# 2_channel_DIP.net
KiCad netlist of a schematic drawn in EAGLE
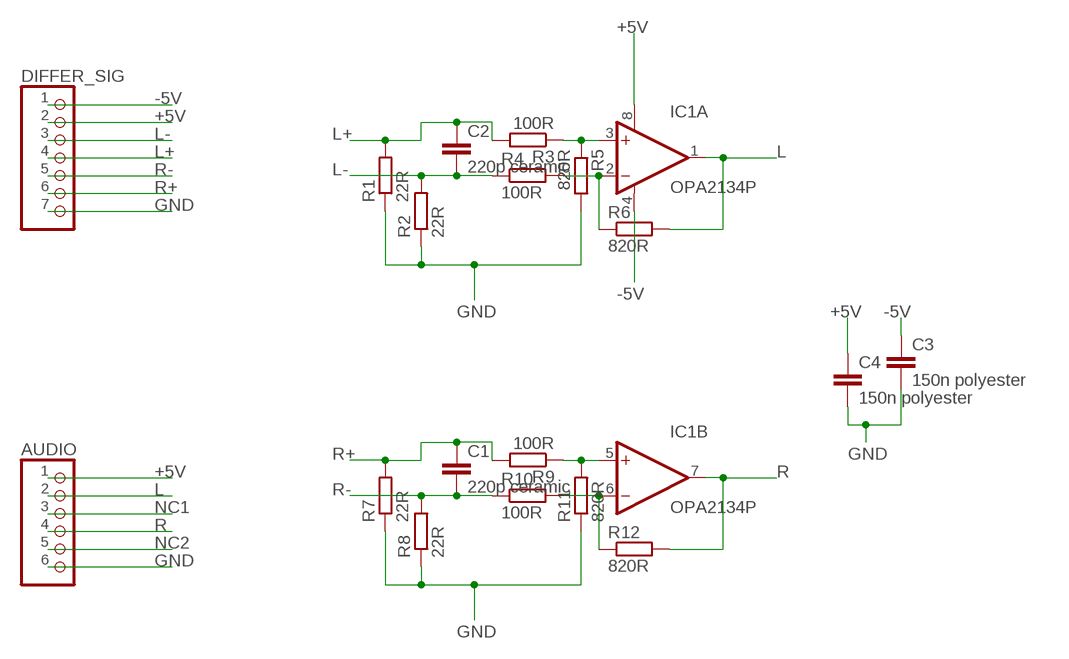
[diagram p0: schematic, sheet 1]

(export (version "E")
  (design (tool "Eeschema 10.0.6"))
  (components
    (comp (ref "AUDIO")
      (value "PINHD-1X6")
      (footprint "eagle-import:1X06")
      (libsource (lib "eagle-import") (part "PINHD-1X6"))
    )
    (comp (ref "C1")
      (value "220p ceramic")
      (footprint "eagle-import:C050-030X075")
      (libsource (lib "eagle-import") (part "C-EU050-030X075"))
    )
    (comp (ref "C2")
      (value "220p ceramic")
      (footprint "eagle-import:C050-030X075")
      (libsource (lib "eagle-import") (part "C-EU050-030X075"))
    )
    (comp (ref "C3")
      (value "150n polyester")
      (footprint "eagle-import:C050-030X075")
      (libsource (lib "eagle-import") (part "C-EU050-030X075"))
    )
    (comp (ref "C4")
      (value "150n polyester")
      (footprint "eagle-import:C050-030X075")
      (libsource (lib "eagle-import") (part "C-EU050-030X075"))
    )
    (comp (ref "DIFFER_SIG")
      (value "PINHD-1X7")
      (footprint "eagle-import:1X07")
      (libsource (lib "eagle-import") (part "PINHD-1X7"))
    )
    (comp (ref "IC1")
      (value "OPA2134P")
      (footprint "eagle-import:DIL08")
      (fields (field (name "MF") "TEXAS INSTRUMENTS") (field (name "MPN") "OPA2134PA"))
      (libsource (lib "eagle-import") (part "OPA2134P"))
    )
    (comp (ref "R1")
      (value "22R")
      (footprint "eagle-import:0207_7")
      (libsource (lib "eagle-import") (part "R-EU_0207/7"))
    )
    (comp (ref "R2")
      (value "22R")
      (footprint "eagle-import:0207_7")
      (libsource (lib "eagle-import") (part "R-EU_0207/7"))
    )
    (comp (ref "R3")
      (value "100R")
      (footprint "eagle-import:0207_7")
      (libsource (lib "eagle-import") (part "R-EU_0207/7"))
    )
    (comp (ref "R4")
      (value "100R")
      (footprint "eagle-import:0207_7")
      (libsource (lib "eagle-import") (part "R-EU_0207/7"))
    )
    (comp (ref "R5")
      (value "820R")
      (footprint "eagle-import:0207_7")
      (libsource (lib "eagle-import") (part "R-EU_0207/7"))
    )
    (comp (ref "R6")
      (value "820R")
      (footprint "eagle-import:0207_7")
      (libsource (lib "eagle-import") (part "R-EU_0207/7"))
    )
    (comp (ref "R7")
      (value "22R")
      (footprint "eagle-import:0207_7")
      (libsource (lib "eagle-import") (part "R-EU_0207/7"))
    )
    (comp (ref "R8")
      (value "22R")
      (footprint "eagle-import:0207_7")
      (libsource (lib "eagle-import") (part "R-EU_0207/7"))
    )
    (comp (ref "R9")
      (value "100R")
      (footprint "eagle-import:0207_7")
      (libsource (lib "eagle-import") (part "R-EU_0207/7"))
    )
    (comp (ref "R10")
      (value "100R")
      (footprint "eagle-import:0207_7")
      (libsource (lib "eagle-import") (part "R-EU_0207/7"))
    )
    (comp (ref "R11")
      (value "820R")
      (footprint "eagle-import:0207_7")
      (libsource (lib "eagle-import") (part "R-EU_0207/7"))
    )
    (comp (ref "R12")
      (value "820R")
      (footprint "eagle-import:0207_7")
      (libsource (lib "eagle-import") (part "R-EU_0207/7"))
    )
  )
  (nets
    (net (code "1") (name "/+5V") (class "Default")
      (node (ref "AUDIO") (pin "1") (pinfunction "1_1") (pintype "passive"))
      (node (ref "C4") (pin "1") (pinfunction "1_1") (pintype "passive"))
      (node (ref "DIFFER_SIG") (pin "2") (pinfunction "2_2") (pintype "passive"))
      (node (ref "IC1") (pin "8") (pinfunction "V+_8") (pintype "power_in"))
    )
    (net (code "2") (name "/-5V") (class "Default")
      (node (ref "C3") (pin "1") (pinfunction "1_1") (pintype "passive"))
      (node (ref "DIFFER_SIG") (pin "1") (pinfunction "1_1") (pintype "passive"))
      (node (ref "IC1") (pin "4") (pinfunction "V-_4") (pintype "power_in"))
    )
    (net (code "3") (name "/GND") (class "Default")
      (node (ref "AUDIO") (pin "6") (pinfunction "6_6") (pintype "passive"))
      (node (ref "C3") (pin "2") (pinfunction "2_2") (pintype "passive"))
      (node (ref "C4") (pin "2") (pinfunction "2_2") (pintype "passive"))
      (node (ref "DIFFER_SIG") (pin "7") (pinfunction "7_7") (pintype "passive"))
      (node (ref "R1") (pin "1") (pinfunction "1_1") (pintype "passive"))
      (node (ref "R11") (pin "1") (pinfunction "1_1") (pintype "passive"))
      (node (ref "R2") (pin "1") (pinfunction "1_1") (pintype "passive"))
      (node (ref "R5") (pin "2") (pinfunction "2_2") (pintype "passive"))
      (node (ref "R7") (pin "1") (pinfunction "1_1") (pintype "passive"))
      (node (ref "R8") (pin "1") (pinfunction "1_1") (pintype "passive"))
    )
    (net (code "4") (name "/L") (class "Default")
      (node (ref "AUDIO") (pin "2") (pinfunction "2_2") (pintype "passive"))
      (node (ref "IC1") (pin "1") (pinfunction "OUT_1") (pintype "output"))
      (node (ref "R6") (pin "2") (pinfunction "2_2") (pintype "passive"))
    )
    (net (code "5") (name "/L+") (class "Default")
      (node (ref "C2") (pin "1") (pinfunction "1_1") (pintype "passive"))
      (node (ref "DIFFER_SIG") (pin "4") (pinfunction "4_4") (pintype "passive"))
      (node (ref "R1") (pin "2") (pinfunction "2_2") (pintype "passive"))
      (node (ref "R3") (pin "2") (pinfunction "2_2") (pintype "passive"))
    )
    (net (code "6") (name "/L-") (class "Default")
      (node (ref "C2") (pin "2") (pinfunction "2_2") (pintype "passive"))
      (node (ref "DIFFER_SIG") (pin "3") (pinfunction "3_3") (pintype "passive"))
      (node (ref "R2") (pin "2") (pinfunction "2_2") (pintype "passive"))
      (node (ref "R4") (pin "1") (pinfunction "1_1") (pintype "passive"))
    )
    (net (code "7") (name "/NC1") (class "Default")
      (node (ref "AUDIO") (pin "3") (pinfunction "3_3") (pintype "passive"))
    )
    (net (code "8") (name "/NC2") (class "Default")
      (node (ref "AUDIO") (pin "5") (pinfunction "5_5") (pintype "passive"))
    )
    (net (code "9") (name "/R") (class "Default")
      (node (ref "AUDIO") (pin "4") (pinfunction "4_4") (pintype "passive"))
      (node (ref "IC1") (pin "7") (pinfunction "OUT_7") (pintype "output"))
      (node (ref "R12") (pin "2") (pinfunction "2_2") (pintype "passive"))
    )
    (net (code "10") (name "/R+") (class "Default")
      (node (ref "C1") (pin "1") (pinfunction "1_1") (pintype "passive"))
      (node (ref "DIFFER_SIG") (pin "6") (pinfunction "6_6") (pintype "passive"))
      (node (ref "R7") (pin "2") (pinfunction "2_2") (pintype "passive"))
      (node (ref "R9") (pin "2") (pinfunction "2_2") (pintype "passive"))
    )
    (net (code "11") (name "/R-") (class "Default")
      (node (ref "C1") (pin "2") (pinfunction "2_2") (pintype "passive"))
      (node (ref "DIFFER_SIG") (pin "5") (pinfunction "5_5") (pintype "passive"))
      (node (ref "R10") (pin "1") (pinfunction "1_1") (pintype "passive"))
      (node (ref "R8") (pin "2") (pinfunction "2_2") (pintype "passive"))
    )
    (net (code "12") (name "Net-(IC1A-+IN)") (class "Default")
      (node (ref "IC1") (pin "3") (pinfunction "+IN_3") (pintype "input"))
      (node (ref "R3") (pin "1") (pinfunction "1_1") (pintype "passive"))
      (node (ref "R5") (pin "1") (pinfunction "1_1") (pintype "passive"))
    )
    (net (code "13") (name "Net-(IC1A--IN)") (class "Default")
      (node (ref "IC1") (pin "2") (pinfunction "-IN_2") (pintype "input"))
      (node (ref "R4") (pin "2") (pinfunction "2_2") (pintype "passive"))
      (node (ref "R6") (pin "1") (pinfunction "1_1") (pintype "passive"))
    )
    (net (code "14") (name "Net-(IC1B-+IN)") (class "Default")
      (node (ref "IC1") (pin "5") (pinfunction "+IN_5") (pintype "input"))
      (node (ref "R11") (pin "2") (pinfunction "2_2") (pintype "passive"))
      (node (ref "R9") (pin "1") (pinfunction "1_1") (pintype "passive"))
    )
    (net (code "15") (name "Net-(IC1B--IN)") (class "Default")
      (node (ref "IC1") (pin "6") (pinfunction "-IN_6") (pintype "input"))
      (node (ref "R10") (pin "2") (pinfunction "2_2") (pintype "passive"))
      (node (ref "R12") (pin "1") (pinfunction "1_1") (pintype "passive"))
    )
  )
)
